# four-leds-shield.net
KiCad netlist of a schematic drawn in EAGLE
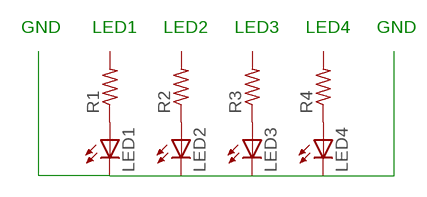
[diagram p0: schematic, sheet 1]

(export (version "E")
  (design (tool "Eeschema 10.0.6"))
  (components
    (comp (ref "LED1")
      (value "LED5MM")
      (footprint "eagle-import:LED5MM")
      (libsource (lib "eagle-import") (part "LED5MM"))
    )
    (comp (ref "LED2")
      (value "LED5MM")
      (footprint "eagle-import:LED5MM")
      (libsource (lib "eagle-import") (part "LED5MM"))
    )
    (comp (ref "LED3")
      (value "LED5MM")
      (footprint "eagle-import:LED5MM")
      (libsource (lib "eagle-import") (part "LED5MM"))
    )
    (comp (ref "LED4")
      (value "LED5MM")
      (footprint "eagle-import:LED5MM")
      (libsource (lib "eagle-import") (part "LED5MM"))
    )
    (comp (ref "R1")
      (value "R-US_0207/12")
      (footprint "eagle-import:0207_12")
      (libsource (lib "eagle-import") (part "R-US_0207/12"))
    )
    (comp (ref "R2")
      (value "R-US_0207/12")
      (footprint "eagle-import:0207_12")
      (libsource (lib "eagle-import") (part "R-US_0207/12"))
    )
    (comp (ref "R3")
      (value "R-US_0207/12")
      (footprint "eagle-import:0207_12")
      (libsource (lib "eagle-import") (part "R-US_0207/12"))
    )
    (comp (ref "R4")
      (value "R-US_0207/12")
      (footprint "eagle-import:0207_12")
      (libsource (lib "eagle-import") (part "R-US_0207/12"))
    )
  )
  (nets
    (net (code "1") (name "Net-(LED1-C)") (class "Default")
      (node (ref "LED1") (pin "K") (pinfunction "C_K") (pintype "passive"))
      (node (ref "LED2") (pin "K") (pinfunction "C_K") (pintype "passive"))
      (node (ref "LED3") (pin "K") (pinfunction "C_K") (pintype "passive"))
      (node (ref "LED4") (pin "K") (pinfunction "C_K") (pintype "passive"))
    )
    (net (code "2") (name "Net-(LED1-PadA)") (class "Default")
      (node (ref "LED1") (pin "A") (pinfunction "A_A") (pintype "passive"))
      (node (ref "R1") (pin "1") (pinfunction "1_1") (pintype "passive"))
    )
    (net (code "3") (name "Net-(LED2-PadA)") (class "Default")
      (node (ref "LED2") (pin "A") (pinfunction "A_A") (pintype "passive"))
      (node (ref "R2") (pin "1") (pinfunction "1_1") (pintype "passive"))
    )
    (net (code "4") (name "Net-(LED3-PadA)") (class "Default")
      (node (ref "LED3") (pin "A") (pinfunction "A_A") (pintype "passive"))
      (node (ref "R3") (pin "1") (pinfunction "1_1") (pintype "passive"))
    )
    (net (code "5") (name "Net-(LED4-PadA)") (class "Default")
      (node (ref "LED4") (pin "A") (pinfunction "A_A") (pintype "passive"))
      (node (ref "R4") (pin "1") (pinfunction "1_1") (pintype "passive"))
    )
    (net (code "6") (name "unconnected-(R1-Pad2)") (class "Default")
      (node (ref "R1") (pin "2") (pinfunction "2_2") (pintype "passive"))
    )
    (net (code "7") (name "unconnected-(R2-Pad2)") (class "Default")
      (node (ref "R2") (pin "2") (pinfunction "2_2") (pintype "passive"))
    )
    (net (code "8") (name "unconnected-(R3-Pad2)") (class "Default")
      (node (ref "R3") (pin "2") (pinfunction "2_2") (pintype "passive"))
    )
    (net (code "9") (name "unconnected-(R4-Pad2)") (class "Default")
      (node (ref "R4") (pin "2") (pinfunction "2_2") (pintype "passive"))
    )
  )
)
